# esp_rot.net
KiCad netlist of a schematic drawn in Altium Designer
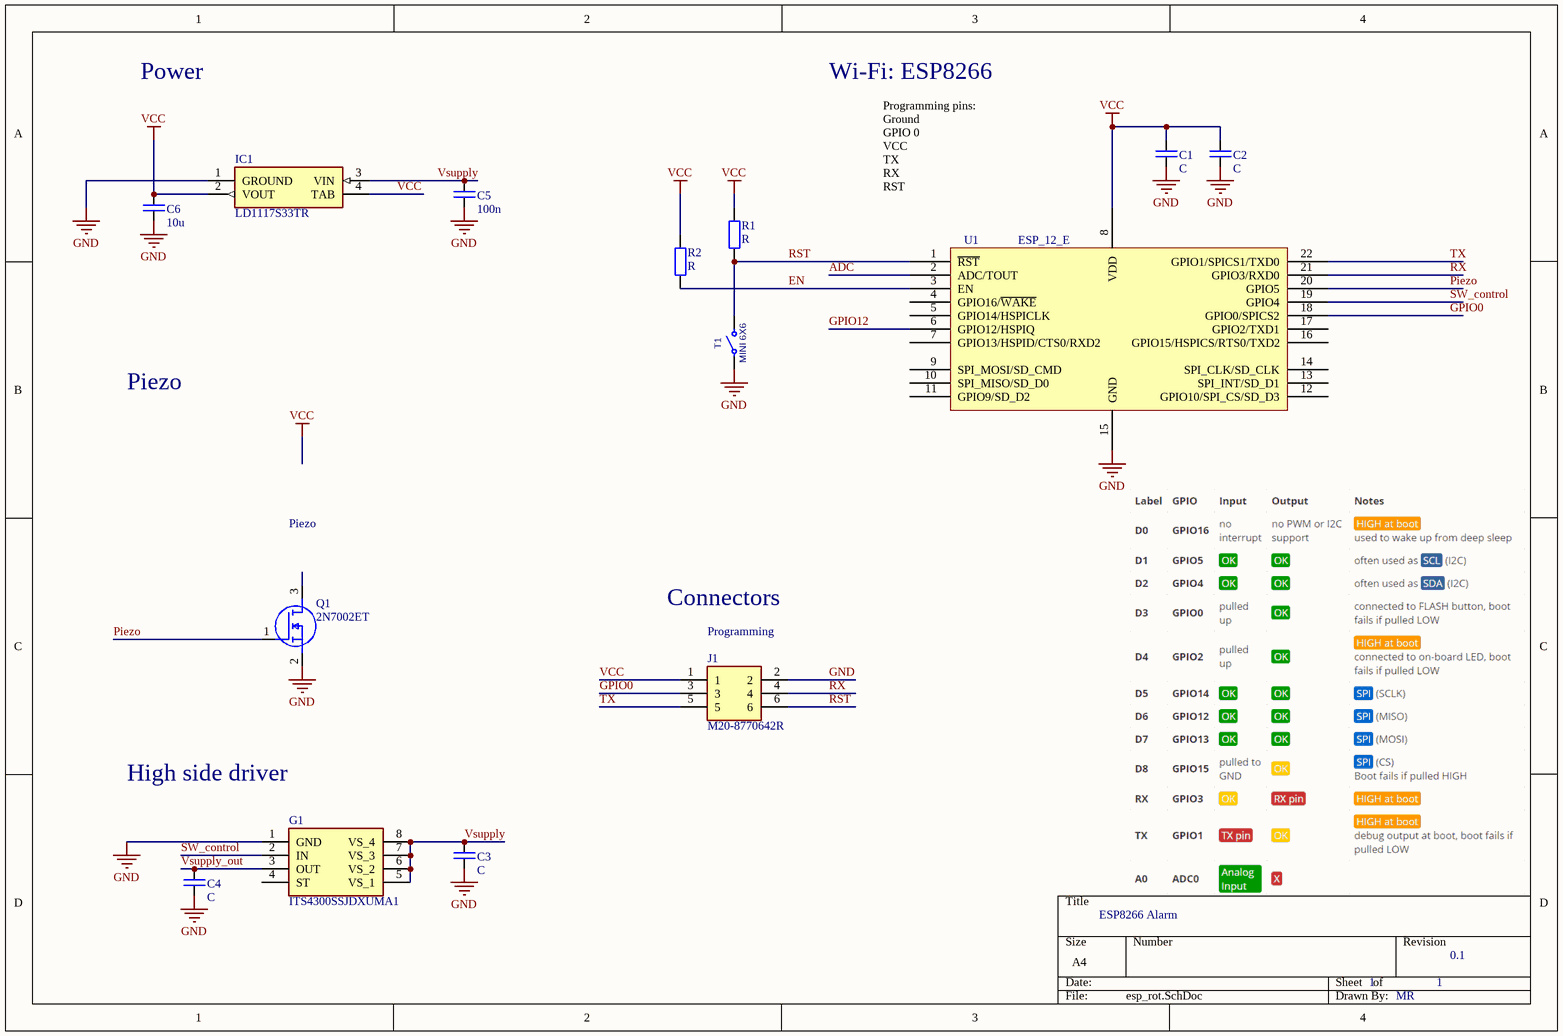
[diagram p0: esp_rot.SchDoc]

(export (version "E")
  (design (tool "Eeschema 10.0.6"))
  (components
    (comp (ref "C1")
      (value "C")
      (footprint "C3216_1206I_M")
      (description "Capacitor")
      (libsource (lib "General") (part "C"))
    )
    (comp (ref "C2")
      (value "C")
      (footprint "C3216_1206I_M")
      (description "Capacitor")
      (libsource (lib "General") (part "C"))
    )
    (comp (ref "C3")
      (value "C")
      (footprint "C3216_1206I_M")
      (description "Capacitor")
      (libsource (lib "General") (part "C"))
    )
    (comp (ref "C4")
      (value "C")
      (footprint "C3216_1206I_M")
      (description "Capacitor")
      (libsource (lib "General") (part "C"))
    )
    (comp (ref "C5")
      (value "100n")
      (footprint "C3216_1206I_M")
      (description "Capacitor")
      (libsource (lib "General") (part "C"))
    )
    (comp (ref "C6")
      (value "10u")
      (footprint "C3216_1206I_M")
      (description "Capacitor")
      (libsource (lib "General") (part "C"))
    )
    (comp (ref "G1")
      (value "ITS4300SSJDXUMA1")
      (footprint "SamacSys:SOIC127P600X175-8N")
      (description "Generator or Oscillator")
      (fields
        (field (name "MOUSER PART NUMBER") "726-ITS4300SSJDXUMA1")
        (field (name "RS PART NUMBER") "1660787")
      )
      (libsource (lib "SamacSys") (part "ITS4300SSJDXUMA1"))
    )
    (comp (ref "IC1")
      (value "LD1117S33TR")
      (footprint "SamacSys:SOT230P700X180-4N")
      (description "Integrated Circuit")
      (fields (field (name "MOUSER PART NUMBER") "511-LD1117S33") (field (name "RS PART NUMBER") "7140697P"))
      (libsource (lib "*") (part "LD1117S33TR"))
    )
    (comp (ref "J1")
      (value "M20-8770642R")
      (footprint "SamacSys:M208770642R")
      (description "Connector")
      (fields (field (name "MOUSER PART NUMBER") "855-M20-8770642R"))
      (libsource (lib "*") (part "M20-8770642R"))
    )
    (comp (ref "Q1")
      (value "2N7002ET")
      (footprint "SamacSys:SOT95P237X101-3N")
      (description "MOSFET (N-Channel)")
      (fields (field (name "RS PART NUMBER") "6900127"))
      (libsource (lib "*") (part "2N7002ET"))
    )
    (comp (ref "R1") (value "R") (footprint "R2012_0805I_M") (libsource (lib "General") (part "R")))
    (comp (ref "R2") (value "R") (footprint "R2012_0805I_M") (libsource (lib "General") (part "R")))
    (comp (ref "T1")
      (value "MINI 6X6")
      (footprint "SW 5x6 SMD SHORT")
      (libsource (lib "Kon_Tipk") (part "MINI 6X6"))
    )
    (comp (ref "U1")
      (value "ESP_12_E")
      (footprint "ESP_12_E")
      (description "ESP-12 Wi-Fi Module by AI-Thinker")
      (libsource (lib "ESP8266") (part "ESP_12_E"))
    )
  )
  (nets
    (net (code "1") (name "/ADC") (class "Default")
      (node (ref "U1") (pin "2") (pinfunction "ADC/TOUT_2") (pintype "passive"))
    )
    (net (code "2") (name "/EN") (class "Default")
      (node (ref "R2") (pin "2") (pintype "passive"))
      (node (ref "U1") (pin "3") (pinfunction "EN_3") (pintype "passive"))
    )
    (net (code "3") (name "/GPIO0") (class "Default")
      (node (ref "J1") (pin "3") (pinfunction "3_3") (pintype "passive"))
      (node (ref "U1") (pin "18") (pinfunction "GPIO0/SPICS2_18") (pintype "passive"))
    )
    (net (code "4") (name "/GPIO12") (class "Default")
      (node (ref "U1") (pin "6") (pinfunction "GPIO12/HSPIQ_6") (pintype "passive"))
    )
    (net (code "5") (name "/Piezo") (class "Default")
      (node (ref "Q1") (pin "1") (pinfunction "G_1") (pintype "passive"))
      (node (ref "U1") (pin "20") (pinfunction "GPIO5_20") (pintype "passive"))
    )
    (net (code "6") (name "/RST") (class "Default")
      (node (ref "J1") (pin "6") (pinfunction "6_6") (pintype "passive"))
      (node (ref "R1") (pin "2") (pintype "passive"))
      (node (ref "T1") (pin "2") (pintype "passive"))
      (node (ref "U1") (pin "1") (pinfunction "~{RST}_1") (pintype "passive"))
    )
    (net (code "7") (name "/RX") (class "Default")
      (node (ref "J1") (pin "4") (pinfunction "4_4") (pintype "passive"))
      (node (ref "U1") (pin "21") (pinfunction "GPIO3/RXD0_21") (pintype "passive"))
    )
    (net (code "8") (name "/SW_control") (class "Default")
      (node (ref "G1") (pin "2") (pinfunction "IN_2") (pintype "passive"))
      (node (ref "U1") (pin "19") (pinfunction "GPIO4_19") (pintype "passive"))
    )
    (net (code "9") (name "/TX") (class "Default")
      (node (ref "J1") (pin "5") (pinfunction "5_5") (pintype "passive"))
      (node (ref "U1") (pin "22") (pinfunction "GPIO1/SPICS1/TXD0_22") (pintype "passive"))
    )
    (net (code "10") (name "/Vsupply") (class "Default")
      (node (ref "C3") (pin "1") (pinfunction "1_1") (pintype "passive"))
      (node (ref "C5") (pin "1") (pinfunction "1_1") (pintype "passive"))
      (node (ref "G1") (pin "5") (pinfunction "VS_1_5") (pintype "passive"))
      (node (ref "G1") (pin "6") (pinfunction "VS_2_6") (pintype "passive"))
      (node (ref "G1") (pin "7") (pinfunction "VS_3_7") (pintype "passive"))
      (node (ref "G1") (pin "8") (pinfunction "VS_4_8") (pintype "passive"))
      (node (ref "IC1") (pin "3") (pinfunction "VIN_3") (pintype "input"))
    )
    (net (code "11") (name "/Vsupply_out") (class "Default")
      (node (ref "C4") (pin "1") (pinfunction "1_1") (pintype "passive"))
      (node (ref "G1") (pin "3") (pinfunction "OUT_3") (pintype "passive"))
    )
    (net (code "12") (name "GND") (class "Default")
      (node (ref "C1") (pin "2") (pinfunction "2_2") (pintype "passive"))
      (node (ref "C2") (pin "2") (pinfunction "2_2") (pintype "passive"))
      (node (ref "C3") (pin "2") (pinfunction "2_2") (pintype "passive"))
      (node (ref "C4") (pin "2") (pinfunction "2_2") (pintype "passive"))
      (node (ref "C5") (pin "2") (pinfunction "2_2") (pintype "passive"))
      (node (ref "C6") (pin "2") (pinfunction "2_2") (pintype "passive"))
      (node (ref "G1") (pin "1") (pinfunction "GND_1") (pintype "passive"))
      (node (ref "IC1") (pin "1") (pinfunction "GROUND_1") (pintype "passive"))
      (node (ref "J1") (pin "2") (pinfunction "2_2") (pintype "passive"))
      (node (ref "Q1") (pin "2") (pinfunction "S_2") (pintype "passive"))
      (node (ref "T1") (pin "1") (pintype "passive"))
      (node (ref "U1") (pin "15") (pinfunction "GND_15") (pintype "passive"))
    )
    (net (code "13") (name "VCC") (class "Default")
      (node (ref "C1") (pin "1") (pinfunction "1_1") (pintype "passive"))
      (node (ref "C2") (pin "1") (pinfunction "1_1") (pintype "passive"))
      (node (ref "C6") (pin "1") (pinfunction "1_1") (pintype "passive"))
      (node (ref "IC1") (pin "2") (pinfunction "VOUT_2") (pintype "output"))
      (node (ref "IC1") (pin "4") (pinfunction "TAB_4") (pintype "passive"))
      (node (ref "J1") (pin "1") (pinfunction "1_1") (pintype "passive"))
      (node (ref "R1") (pin "1") (pintype "passive"))
      (node (ref "R2") (pin "1") (pintype "passive"))
      (node (ref "U1") (pin "8") (pinfunction "VDD_8") (pintype "passive"))
    )
    (net (code "14") (name "unconnected-(G1-ST-Pad4)") (class "Default")
      (node (ref "G1") (pin "4") (pinfunction "ST_4") (pintype "passive"))
    )
    (net (code "15") (name "unconnected-(Q1-D-Pad3)") (class "Default")
      (node (ref "Q1") (pin "3") (pinfunction "D_3") (pintype "passive"))
    )
    (net (code "16") (name "unconnected-(U1-GPIO2{slash}TXD1-Pad17)") (class "Default")
      (node (ref "U1") (pin "17") (pinfunction "GPIO2/TXD1_17") (pintype "passive"))
    )
    (net (code "17") (name "unconnected-(U1-GPIO9{slash}SD_D2-Pad11)") (class "Default")
      (node (ref "U1") (pin "11") (pinfunction "GPIO9/SD_D2_11") (pintype "passive"))
    )
    (net (code "18") (name "unconnected-(U1-GPIO10{slash}SPI_CS{slash}SD_D3-Pad12)") (class "Default")
      (node (ref "U1") (pin "12") (pinfunction "GPIO10/SPI_CS/SD_D3_12") (pintype "passive"))
    )
    (net (code "19") (name "unconnected-(U1-GPIO13{slash}HSPID{slash}CTS0{slash}RXD2-Pad7)") (class "Default")
      (node (ref "U1") (pin "7") (pinfunction "GPIO13/HSPID/CTS0/RXD2_7") (pintype "passive"))
    )
    (net (code "20") (name "unconnected-(U1-GPIO14{slash}HSPICLK-Pad5)") (class "Default")
      (node (ref "U1") (pin "5") (pinfunction "GPIO14/HSPICLK_5") (pintype "passive"))
    )
    (net (code "21") (name "unconnected-(U1-GPIO15{slash}HSPICS{slash}RTS0{slash}TXD2-Pad16)") (class "Default")
      (node (ref "U1") (pin "16") (pinfunction "GPIO15/HSPICS/RTS0/TXD2_16") (pintype "passive"))
    )
    (net (code "22") (name "unconnected-(U1-GPIO16{slash}~{WAKE}-Pad4)") (class "Default")
      (node (ref "U1") (pin "4") (pinfunction "GPIO16/~{WAKE}_4") (pintype "passive"))
    )
    (net (code "23") (name "unconnected-(U1-SPI_CLK{slash}SD_CLK-Pad14)") (class "Default")
      (node (ref "U1") (pin "14") (pinfunction "SPI_CLK/SD_CLK_14") (pintype "passive"))
    )
    (net (code "24") (name "unconnected-(U1-SPI_INT{slash}SD_D1-Pad13)") (class "Default")
      (node (ref "U1") (pin "13") (pinfunction "SPI_INT/SD_D1_13") (pintype "passive"))
    )
    (net (code "25") (name "unconnected-(U1-SPI_MISO{slash}SD_D0-Pad10)") (class "Default")
      (node (ref "U1") (pin "10") (pinfunction "SPI_MISO/SD_D0_10") (pintype "passive"))
    )
    (net (code "26") (name "unconnected-(U1-SPI_MOSI{slash}SD_CMD-Pad9)") (class "Default")
      (node (ref "U1") (pin "9") (pinfunction "SPI_MOSI/SD_CMD_9") (pintype "passive"))
    )
  )
)
